# main.net
KiCad netlist of a schematic drawn in EAGLE
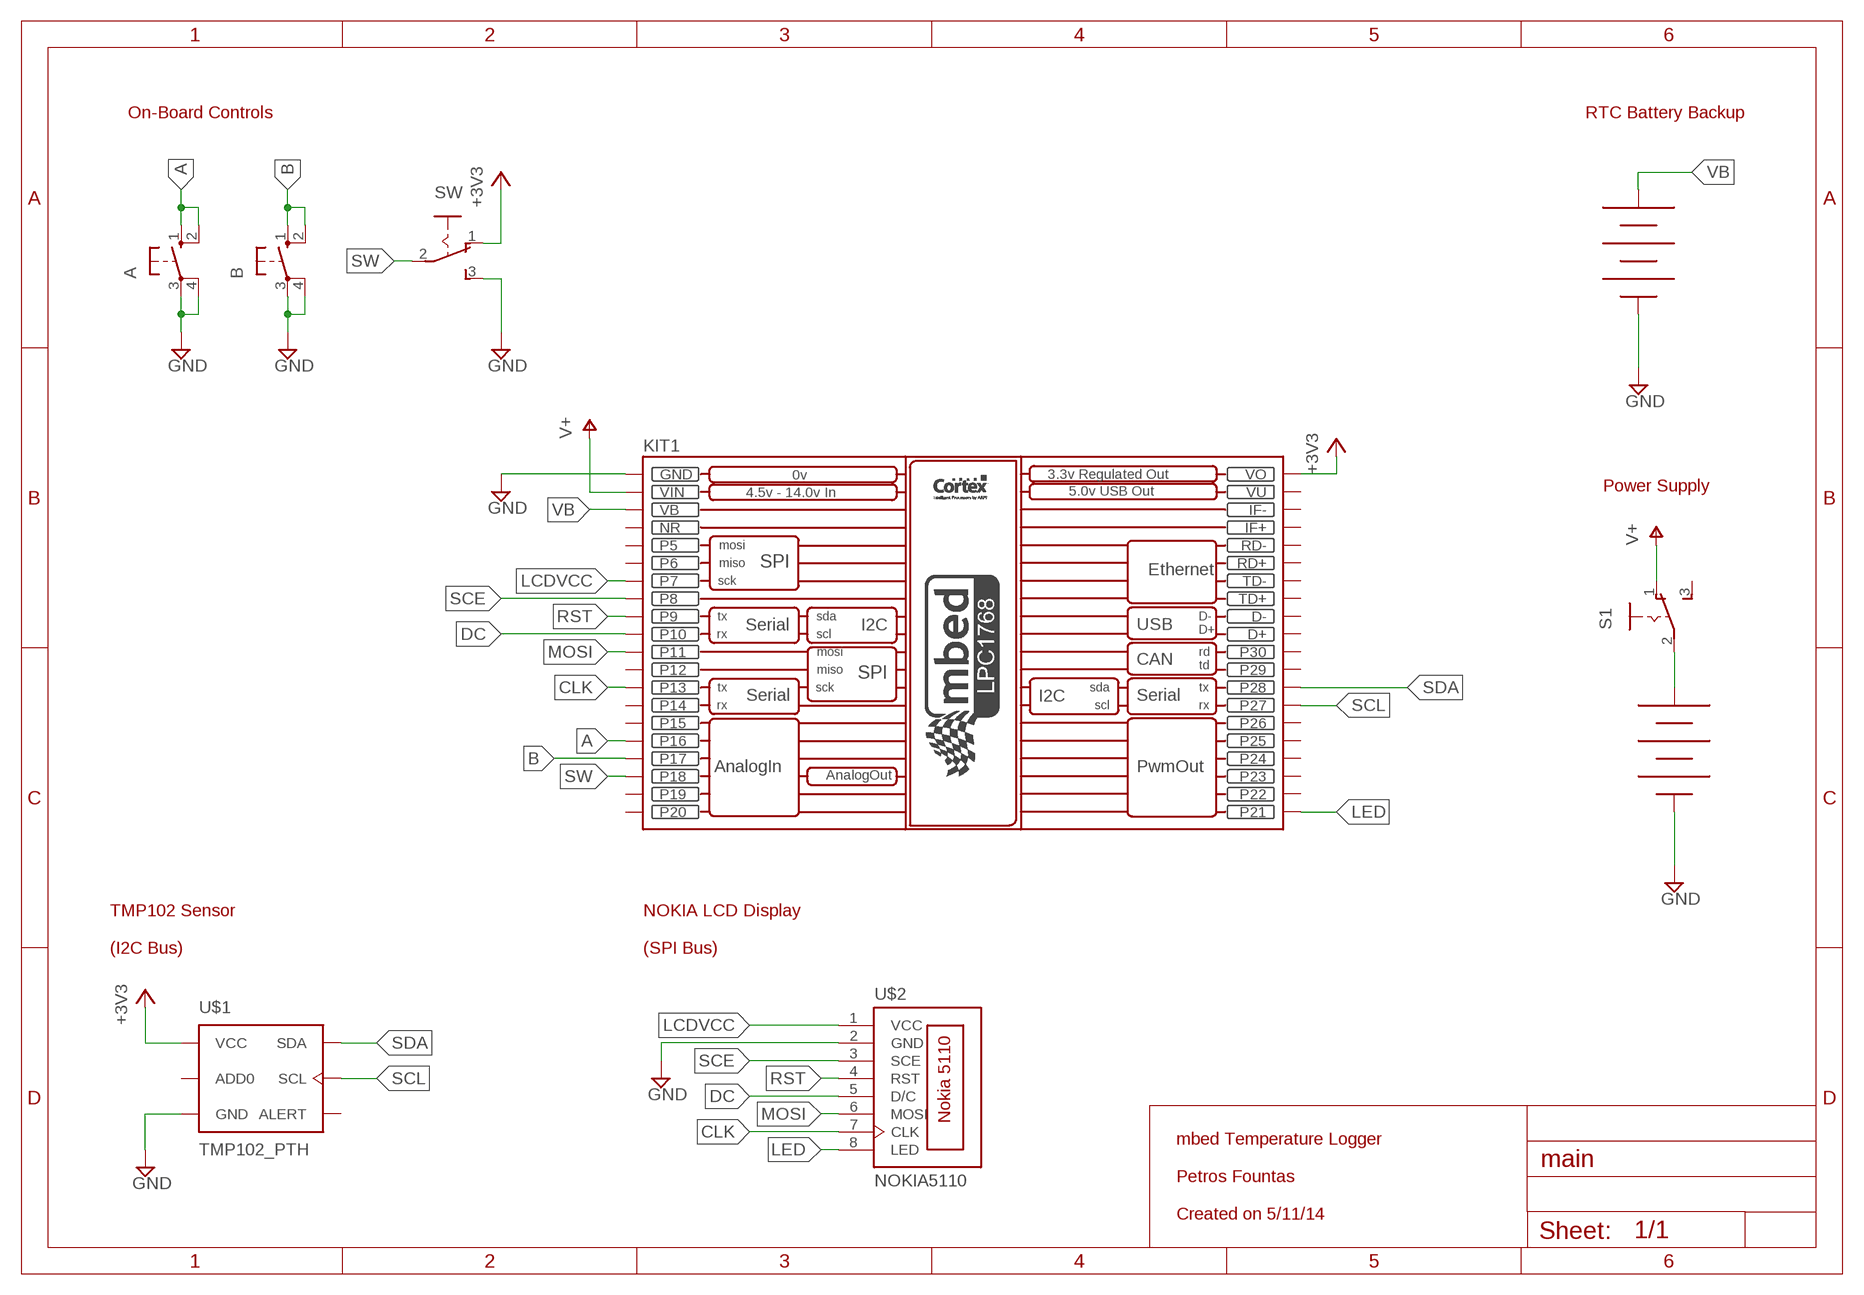
[diagram p0: schematic, sheet 1]

(export (version "E")
  (design (tool "Eeschema 10.0.6"))
  (components
    (comp (ref "A")
      (value "BUTTON_THT")
      (footprint "eagle-import:BUTTON")
      (fields (field (name "MPN") "B3F-1000"))
      (libsource (lib "eagle-import") (part "BUTTON_THT"))
    )
    (comp (ref "B")
      (value "BUTTON_THT")
      (footprint "eagle-import:BUTTON")
      (fields (field (name "MPN") "B3F-1000"))
      (libsource (lib "eagle-import") (part "BUTTON_THT"))
    )
    (comp (ref "BATT1")
      (value "BATTERY_4AA")
      (footprint "eagle-import:BATTERY_4AA")
      (libsource (lib "eagle-import") (part "BATTERY_4AA"))
    )
    (comp (ref "BATT2")
      (value "BATTERY_H_CR2032")
      (footprint "eagle-import:BATTERY_H")
      (libsource (lib "eagle-import") (part "BATTERY_H_CR2032"))
    )
    (comp (ref "KIT1")
      (value "MBED_SILK")
      (footprint "eagle-import:MBED")
      (libsource (lib "eagle-import") (part "MBED_SILK"))
    )
    (comp (ref "S1")
      (value "M251")
      (footprint "eagle-import:M251")
      (libsource (lib "eagle-import") (part "M251"))
    )
    (comp (ref "SW")
      (value "M251")
      (footprint "eagle-import:M251")
      (libsource (lib "eagle-import") (part "M251"))
    )
    (comp (ref "U$1")
      (value "TMP102_PTH")
      (footprint "eagle-import:TMP102")
      (libsource (lib "eagle-import") (part "TMP102_PTH"))
    )
    (comp (ref "U$2")
      (value "NOKIA5110")
      (footprint "eagle-import:NOKIA5110")
      (libsource (lib "eagle-import") (part "NOKIA5110"))
    )
  )
  (nets
    (net (code "1") (name "+3V3") (class "Default")
      (node (ref "KIT1") (pin "VOUT") (pinfunction "VO_VOUT") (pintype "power_in"))
      (node (ref "SW") (pin "1") (pinfunction "O_1") (pintype "passive"))
      (node (ref "U$1") (pin "VCC") (pinfunction "VCC_VCC") (pintype "power_in"))
    )
    (net (code "2") (name "/NR") (class "Default")
      (node (ref "KIT1") (pin "NR") (pinfunction "NR_NR") (pintype "power_in"))
    )
    (net (code "3") (name "/VU") (class "Default")
      (node (ref "KIT1") (pin "VU") (pinfunction "VU_VU") (pintype "power_in"))
    )
    (net (code "4") (name "A") (class "Default")
      (node (ref "A") (pin "1") (pinfunction "S_1") (pintype "passive"))
      (node (ref "A") (pin "2") (pinfunction "S1_2") (pintype "passive"))
      (node (ref "KIT1") (pin "P$16") (pinfunction "P16_P$16") (pintype "bidirectional"))
    )
    (net (code "5") (name "B") (class "Default")
      (node (ref "B") (pin "1") (pinfunction "S_1") (pintype "passive"))
      (node (ref "B") (pin "2") (pinfunction "S1_2") (pintype "passive"))
      (node (ref "KIT1") (pin "P$17") (pinfunction "P17_P$17") (pintype "bidirectional"))
    )
    (net (code "6") (name "CLK") (class "Default")
      (node (ref "KIT1") (pin "P$13") (pinfunction "P13_P$13") (pintype "bidirectional"))
      (node (ref "U$2") (pin "7") (pinfunction "CLK_7") (pintype "input"))
    )
    (net (code "7") (name "DC") (class "Default")
      (node (ref "KIT1") (pin "P$10") (pinfunction "P10_P$10") (pintype "bidirectional"))
      (node (ref "U$2") (pin "5") (pinfunction "D/C_5") (pintype "input"))
    )
    (net (code "8") (name "GND") (class "Default")
      (node (ref "A") (pin "3") (pinfunction "P_3") (pintype "passive"))
      (node (ref "A") (pin "4") (pinfunction "P1_4") (pintype "passive"))
      (node (ref "B") (pin "3") (pinfunction "P_3") (pintype "passive"))
      (node (ref "B") (pin "4") (pinfunction "P1_4") (pintype "passive"))
      (node (ref "BATT1") (pin "-") (pinfunction "-_-") (pintype "bidirectional"))
      (node (ref "BATT2") (pin "-") (pinfunction "-_-") (pintype "bidirectional"))
      (node (ref "KIT1") (pin "GND") (pinfunction "GND_GND") (pintype "power_in"))
      (node (ref "SW") (pin "3") (pinfunction "S_3") (pintype "passive"))
      (node (ref "U$1") (pin "GND") (pinfunction "GND_GND") (pintype "power_in"))
      (node (ref "U$2") (pin "2") (pinfunction "GND_2") (pintype "power_in"))
    )
    (net (code "9") (name "LCDVCC") (class "Default")
      (node (ref "KIT1") (pin "P$7") (pinfunction "P7_P$7") (pintype "bidirectional"))
      (node (ref "U$2") (pin "1") (pinfunction "VCC_1") (pintype "power_in"))
    )
    (net (code "10") (name "LED") (class "Default")
      (node (ref "KIT1") (pin "P$21") (pinfunction "P21_P$21") (pintype "bidirectional"))
      (node (ref "U$2") (pin "8") (pinfunction "LED_8") (pintype "input"))
    )
    (net (code "11") (name "MOSI") (class "Default")
      (node (ref "KIT1") (pin "P$11") (pinfunction "P11_P$11") (pintype "bidirectional"))
      (node (ref "U$2") (pin "6") (pinfunction "MOSI_6") (pintype "input"))
    )
    (net (code "12") (name "Net-(S1-P)") (class "Default")
      (node (ref "BATT1") (pin "+") (pinfunction "+_+") (pintype "bidirectional"))
      (node (ref "S1") (pin "2") (pinfunction "P_2") (pintype "passive"))
    )
    (net (code "13") (name "RST") (class "Default")
      (node (ref "KIT1") (pin "P$9") (pinfunction "P9_P$9") (pintype "bidirectional"))
      (node (ref "U$2") (pin "4") (pinfunction "RST_4") (pintype "input"))
    )
    (net (code "14") (name "SCE") (class "Default")
      (node (ref "KIT1") (pin "P$8") (pinfunction "P8_P$8") (pintype "bidirectional"))
      (node (ref "U$2") (pin "3") (pinfunction "SCE_3") (pintype "input"))
    )
    (net (code "15") (name "SCL") (class "Default")
      (node (ref "KIT1") (pin "P$27") (pinfunction "P27_P$27") (pintype "bidirectional"))
      (node (ref "U$1") (pin "SCL") (pinfunction "SCL_SCL") (pintype "input"))
    )
    (net (code "16") (name "SDA") (class "Default")
      (node (ref "KIT1") (pin "P$28") (pinfunction "P28_P$28") (pintype "bidirectional"))
      (node (ref "U$1") (pin "SDA") (pinfunction "SDA_SDA") (pintype "bidirectional"))
    )
    (net (code "17") (name "SW") (class "Default")
      (node (ref "KIT1") (pin "P$18") (pinfunction "P18_P$18") (pintype "bidirectional"))
      (node (ref "SW") (pin "2") (pinfunction "P_2") (pintype "passive"))
    )
    (net (code "18") (name "V+") (class "Default")
      (node (ref "KIT1") (pin "VIN") (pinfunction "VIN_VIN") (pintype "power_in"))
      (node (ref "S1") (pin "1") (pinfunction "O_1") (pintype "passive"))
    )
    (net (code "19") (name "VB") (class "Default")
      (node (ref "BATT2") (pin "+") (pinfunction "+_+") (pintype "bidirectional"))
      (node (ref "KIT1") (pin "VB") (pinfunction "VB_VB") (pintype "power_in"))
    )
    (net (code "20") (name "unconnected-(KIT1-P5-PadP$5)") (class "Default")
      (node (ref "KIT1") (pin "P$5") (pinfunction "P5_P$5") (pintype "bidirectional"))
    )
    (net (code "21") (name "unconnected-(KIT1-P6-PadP$6)") (class "Default")
      (node (ref "KIT1") (pin "P$6") (pinfunction "P6_P$6") (pintype "bidirectional"))
    )
    (net (code "22") (name "unconnected-(KIT1-P12-PadP$12)") (class "Default")
      (node (ref "KIT1") (pin "P$12") (pinfunction "P12_P$12") (pintype "bidirectional"))
    )
    (net (code "23") (name "unconnected-(KIT1-P14-PadP$14)") (class "Default")
      (node (ref "KIT1") (pin "P$14") (pinfunction "P14_P$14") (pintype "bidirectional"))
    )
    (net (code "24") (name "unconnected-(KIT1-P15-PadP$15)") (class "Default")
      (node (ref "KIT1") (pin "P$15") (pinfunction "P15_P$15") (pintype "bidirectional"))
    )
    (net (code "25") (name "unconnected-(KIT1-P19-PadP$19)") (class "Default")
      (node (ref "KIT1") (pin "P$19") (pinfunction "P19_P$19") (pintype "bidirectional"))
    )
    (net (code "26") (name "unconnected-(KIT1-P20-PadP$20)") (class "Default")
      (node (ref "KIT1") (pin "P$20") (pinfunction "P20_P$20") (pintype "bidirectional"))
    )
    (net (code "27") (name "unconnected-(KIT1-P22-PadP$22)") (class "Default")
      (node (ref "KIT1") (pin "P$22") (pinfunction "P22_P$22") (pintype "bidirectional"))
    )
    (net (code "28") (name "unconnected-(KIT1-P23-PadP$23)") (class "Default")
      (node (ref "KIT1") (pin "P$23") (pinfunction "P23_P$23") (pintype "bidirectional"))
    )
    (net (code "29") (name "unconnected-(KIT1-P24-PadP$24)") (class "Default")
      (node (ref "KIT1") (pin "P$24") (pinfunction "P24_P$24") (pintype "bidirectional"))
    )
    (net (code "30") (name "unconnected-(KIT1-P25-PadP$25)") (class "Default")
      (node (ref "KIT1") (pin "P$25") (pinfunction "P25_P$25") (pintype "bidirectional"))
    )
    (net (code "31") (name "unconnected-(KIT1-P26-PadP$26)") (class "Default")
      (node (ref "KIT1") (pin "P$26") (pinfunction "P26_P$26") (pintype "bidirectional"))
    )
    (net (code "32") (name "unconnected-(KIT1-P29-PadP$29)") (class "Default")
      (node (ref "KIT1") (pin "P$29") (pinfunction "P29_P$29") (pintype "bidirectional"))
    )
    (net (code "33") (name "unconnected-(KIT1-P30-PadP$30)") (class "Default")
      (node (ref "KIT1") (pin "P$30") (pinfunction "P30_P$30") (pintype "bidirectional"))
    )
    (net (code "34") (name "unconnected-(KIT1-PadD+)") (class "Default")
      (node (ref "KIT1") (pin "D+") (pinfunction "D+_D+") (pintype "bidirectional"))
    )
    (net (code "35") (name "unconnected-(KIT1-PadD-)") (class "Default")
      (node (ref "KIT1") (pin "D-") (pinfunction "D-_D-") (pintype "bidirectional"))
    )
    (net (code "36") (name "unconnected-(KIT1-PadIF+)") (class "Default")
      (node (ref "KIT1") (pin "IF+") (pinfunction "IF+_IF+") (pintype "bidirectional"))
    )
    (net (code "37") (name "unconnected-(KIT1-PadIF-)") (class "Default")
      (node (ref "KIT1") (pin "IF-") (pinfunction "IF-_IF-") (pintype "bidirectional"))
    )
    (net (code "38") (name "unconnected-(KIT1-PadRD+)") (class "Default")
      (node (ref "KIT1") (pin "RD+") (pinfunction "RD+_RD+") (pintype "bidirectional"))
    )
    (net (code "39") (name "unconnected-(KIT1-PadRD-)") (class "Default")
      (node (ref "KIT1") (pin "RD-") (pinfunction "RD-_RD-") (pintype "bidirectional"))
    )
    (net (code "40") (name "unconnected-(KIT1-PadTD+)") (class "Default")
      (node (ref "KIT1") (pin "TD+") (pinfunction "TD+_TD+") (pintype "bidirectional"))
    )
    (net (code "41") (name "unconnected-(KIT1-PadTD-)") (class "Default")
      (node (ref "KIT1") (pin "TD-") (pinfunction "TD-_TD-") (pintype "bidirectional"))
    )
    (net (code "42") (name "unconnected-(S1-S-Pad3)") (class "Default")
      (node (ref "S1") (pin "3") (pinfunction "S_3") (pintype "passive"))
    )
    (net (code "43") (name "unconnected-(U$1-PadADD0)") (class "Default")
      (node (ref "U$1") (pin "ADD0") (pinfunction "ADD0_ADD0") (pintype "input"))
    )
    (net (code "44") (name "unconnected-(U$1-PadALERT)") (class "Default")
      (node (ref "U$1") (pin "ALERT") (pinfunction "ALERT_ALERT") (pintype "output"))
    )
  )
)
